# valveconn.net
KiCad netlist of a schematic drawn in Altium Designer
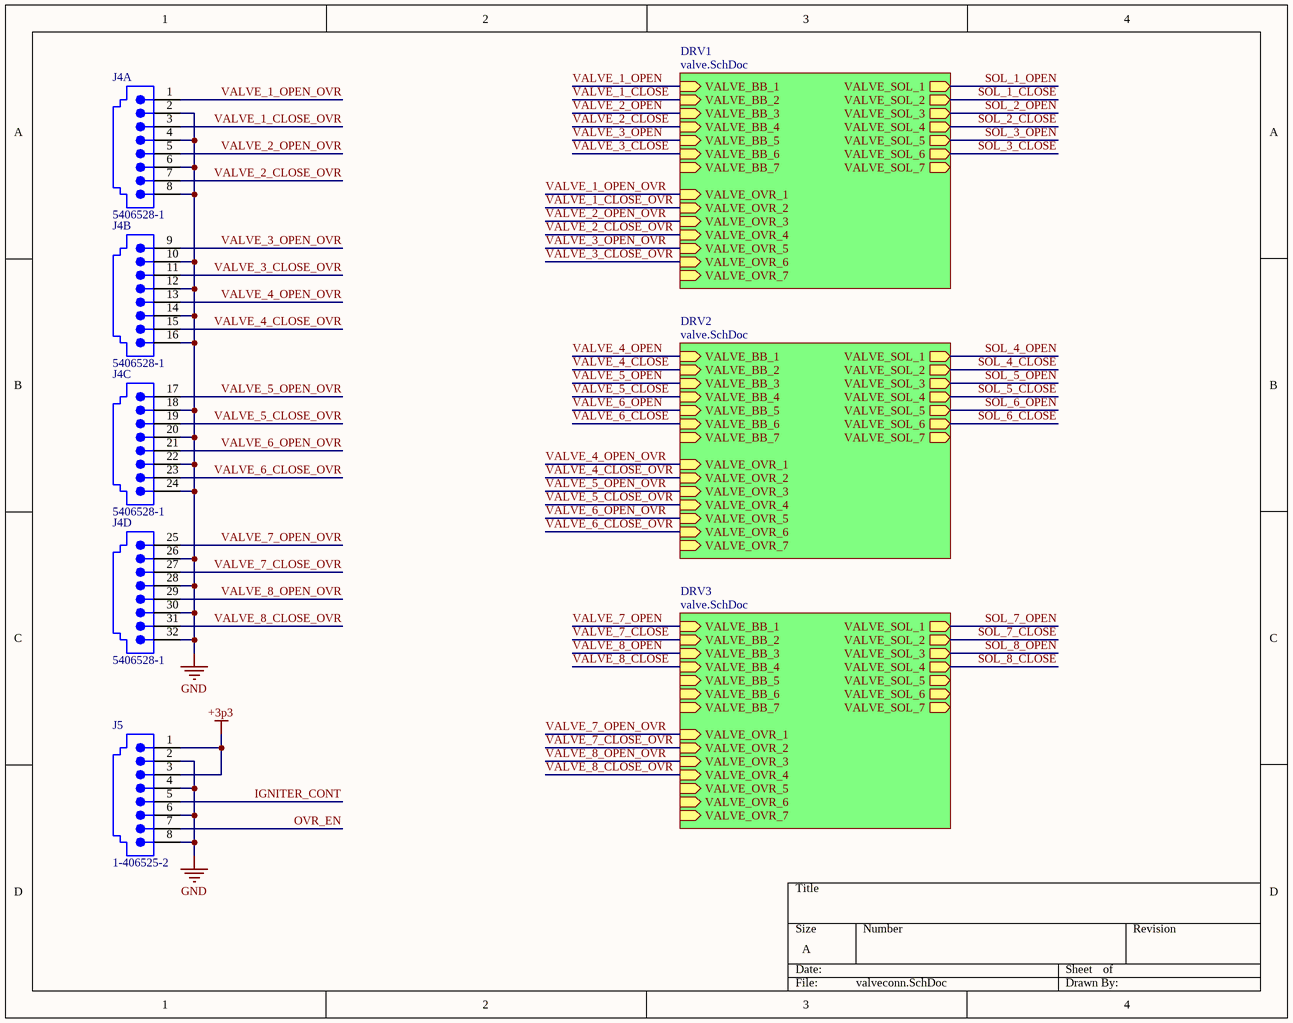
[diagram p0: valveconn.SchDoc]

(export (version "E")
  (design (tool "Eeschema 10.0.6"))
  (components
    (comp (ref "J4")
      (value "5406528-1")
      (footprint "5406528-1")
      (description "4 port RJ45")
      (libsource (lib "PARSEC") (part "5406528-1"))
    )
    (comp (ref "J5")
      (value "1-406525-2")
      (footprint "1-406525-2")
      (description "1 port RJ45")
      (libsource (lib "PARSEC") (part "1-406525-2"))
    )
  )
  (nets
    (net (code "1") (name "+3p3") (class "Default")
      (node (ref "J5") (pin "1") (pinfunction "1_1") (pintype "passive"))
      (node (ref "J5") (pin "3") (pinfunction "3_3") (pintype "passive"))
    )
    (net (code "2") (name "/IGNITER_CONT") (class "Default")
      (node (ref "J5") (pin "5") (pinfunction "5_5") (pintype "passive"))
    )
    (net (code "3") (name "/OVR_EN") (class "Default")
      (node (ref "J5") (pin "7") (pinfunction "7_7") (pintype "passive"))
    )
    (net (code "21") (name "/VALVE_1_CLOSE_OVR") (class "Default")
      (node (ref "J4") (pin "3") (pinfunction "3_3") (pintype "passive"))
    )
    (net (code "23") (name "/VALVE_1_OPEN_OVR") (class "Default")
      (node (ref "J4") (pin "1") (pinfunction "1_1") (pintype "passive"))
    )
    (net (code "25") (name "/VALVE_2_CLOSE_OVR") (class "Default")
      (node (ref "J4") (pin "7") (pinfunction "7_7") (pintype "passive"))
    )
    (net (code "27") (name "/VALVE_2_OPEN_OVR") (class "Default")
      (node (ref "J4") (pin "5") (pinfunction "5_5") (pintype "passive"))
    )
    (net (code "29") (name "/VALVE_3_CLOSE_OVR") (class "Default")
      (node (ref "J4") (pin "11") (pinfunction "11_11") (pintype "passive"))
    )
    (net (code "31") (name "/VALVE_3_OPEN_OVR") (class "Default")
      (node (ref "J4") (pin "9") (pinfunction "9_9") (pintype "passive"))
    )
    (net (code "33") (name "/VALVE_4_CLOSE_OVR") (class "Default")
      (node (ref "J4") (pin "15") (pinfunction "15_15") (pintype "passive"))
    )
    (net (code "35") (name "/VALVE_4_OPEN_OVR") (class "Default")
      (node (ref "J4") (pin "13") (pinfunction "13_13") (pintype "passive"))
    )
    (net (code "37") (name "/VALVE_5_CLOSE_OVR") (class "Default")
      (node (ref "J4") (pin "19") (pinfunction "19_19") (pintype "passive"))
    )
    (net (code "39") (name "/VALVE_5_OPEN_OVR") (class "Default")
      (node (ref "J4") (pin "17") (pinfunction "17_17") (pintype "passive"))
    )
    (net (code "41") (name "/VALVE_6_CLOSE_OVR") (class "Default")
      (node (ref "J4") (pin "23") (pinfunction "23_23") (pintype "passive"))
    )
    (net (code "43") (name "/VALVE_6_OPEN_OVR") (class "Default")
      (node (ref "J4") (pin "21") (pinfunction "21_21") (pintype "passive"))
    )
    (net (code "45") (name "/VALVE_7_CLOSE_OVR") (class "Default")
      (node (ref "J4") (pin "27") (pinfunction "27_27") (pintype "passive"))
    )
    (net (code "47") (name "/VALVE_7_OPEN_OVR") (class "Default")
      (node (ref "J4") (pin "25") (pinfunction "25_25") (pintype "passive"))
    )
    (net (code "49") (name "/VALVE_8_CLOSE_OVR") (class "Default")
      (node (ref "J4") (pin "31") (pinfunction "31_31") (pintype "passive"))
    )
    (net (code "51") (name "/VALVE_8_OPEN_OVR") (class "Default")
      (node (ref "J4") (pin "29") (pinfunction "29_29") (pintype "passive"))
    )
    (net (code "67") (name "GND") (class "Default")
      (node (ref "J4") (pin "10") (pinfunction "10_10") (pintype "passive"))
      (node (ref "J4") (pin "12") (pinfunction "12_12") (pintype "passive"))
      (node (ref "J4") (pin "14") (pinfunction "14_14") (pintype "passive"))
      (node (ref "J4") (pin "16") (pinfunction "16_16") (pintype "passive"))
      (node (ref "J4") (pin "18") (pinfunction "18_18") (pintype "passive"))
      (node (ref "J4") (pin "2") (pinfunction "2_2") (pintype "passive"))
      (node (ref "J4") (pin "20") (pinfunction "20_20") (pintype "passive"))
      (node (ref "J4") (pin "22") (pinfunction "22_22") (pintype "passive"))
      (node (ref "J4") (pin "24") (pinfunction "24_24") (pintype "passive"))
      (node (ref "J4") (pin "26") (pinfunction "26_26") (pintype "passive"))
      (node (ref "J4") (pin "28") (pinfunction "28_28") (pintype "passive"))
      (node (ref "J4") (pin "30") (pinfunction "30_30") (pintype "passive"))
      (node (ref "J4") (pin "32") (pinfunction "32_32") (pintype "passive"))
      (node (ref "J4") (pin "4") (pinfunction "4_4") (pintype "passive"))
      (node (ref "J4") (pin "6") (pinfunction "6_6") (pintype "passive"))
      (node (ref "J4") (pin "8") (pinfunction "8_8") (pintype "passive"))
      (node (ref "J5") (pin "2") (pinfunction "2_2") (pintype "passive"))
      (node (ref "J5") (pin "4") (pinfunction "4_4") (pintype "passive"))
      (node (ref "J5") (pin "6") (pinfunction "6_6") (pintype "passive"))
      (node (ref "J5") (pin "8") (pinfunction "8_8") (pintype "passive"))
    )
  )
)
